# TTL_CAN.net
KiCad netlist of a schematic drawn in EasyEDA Pro
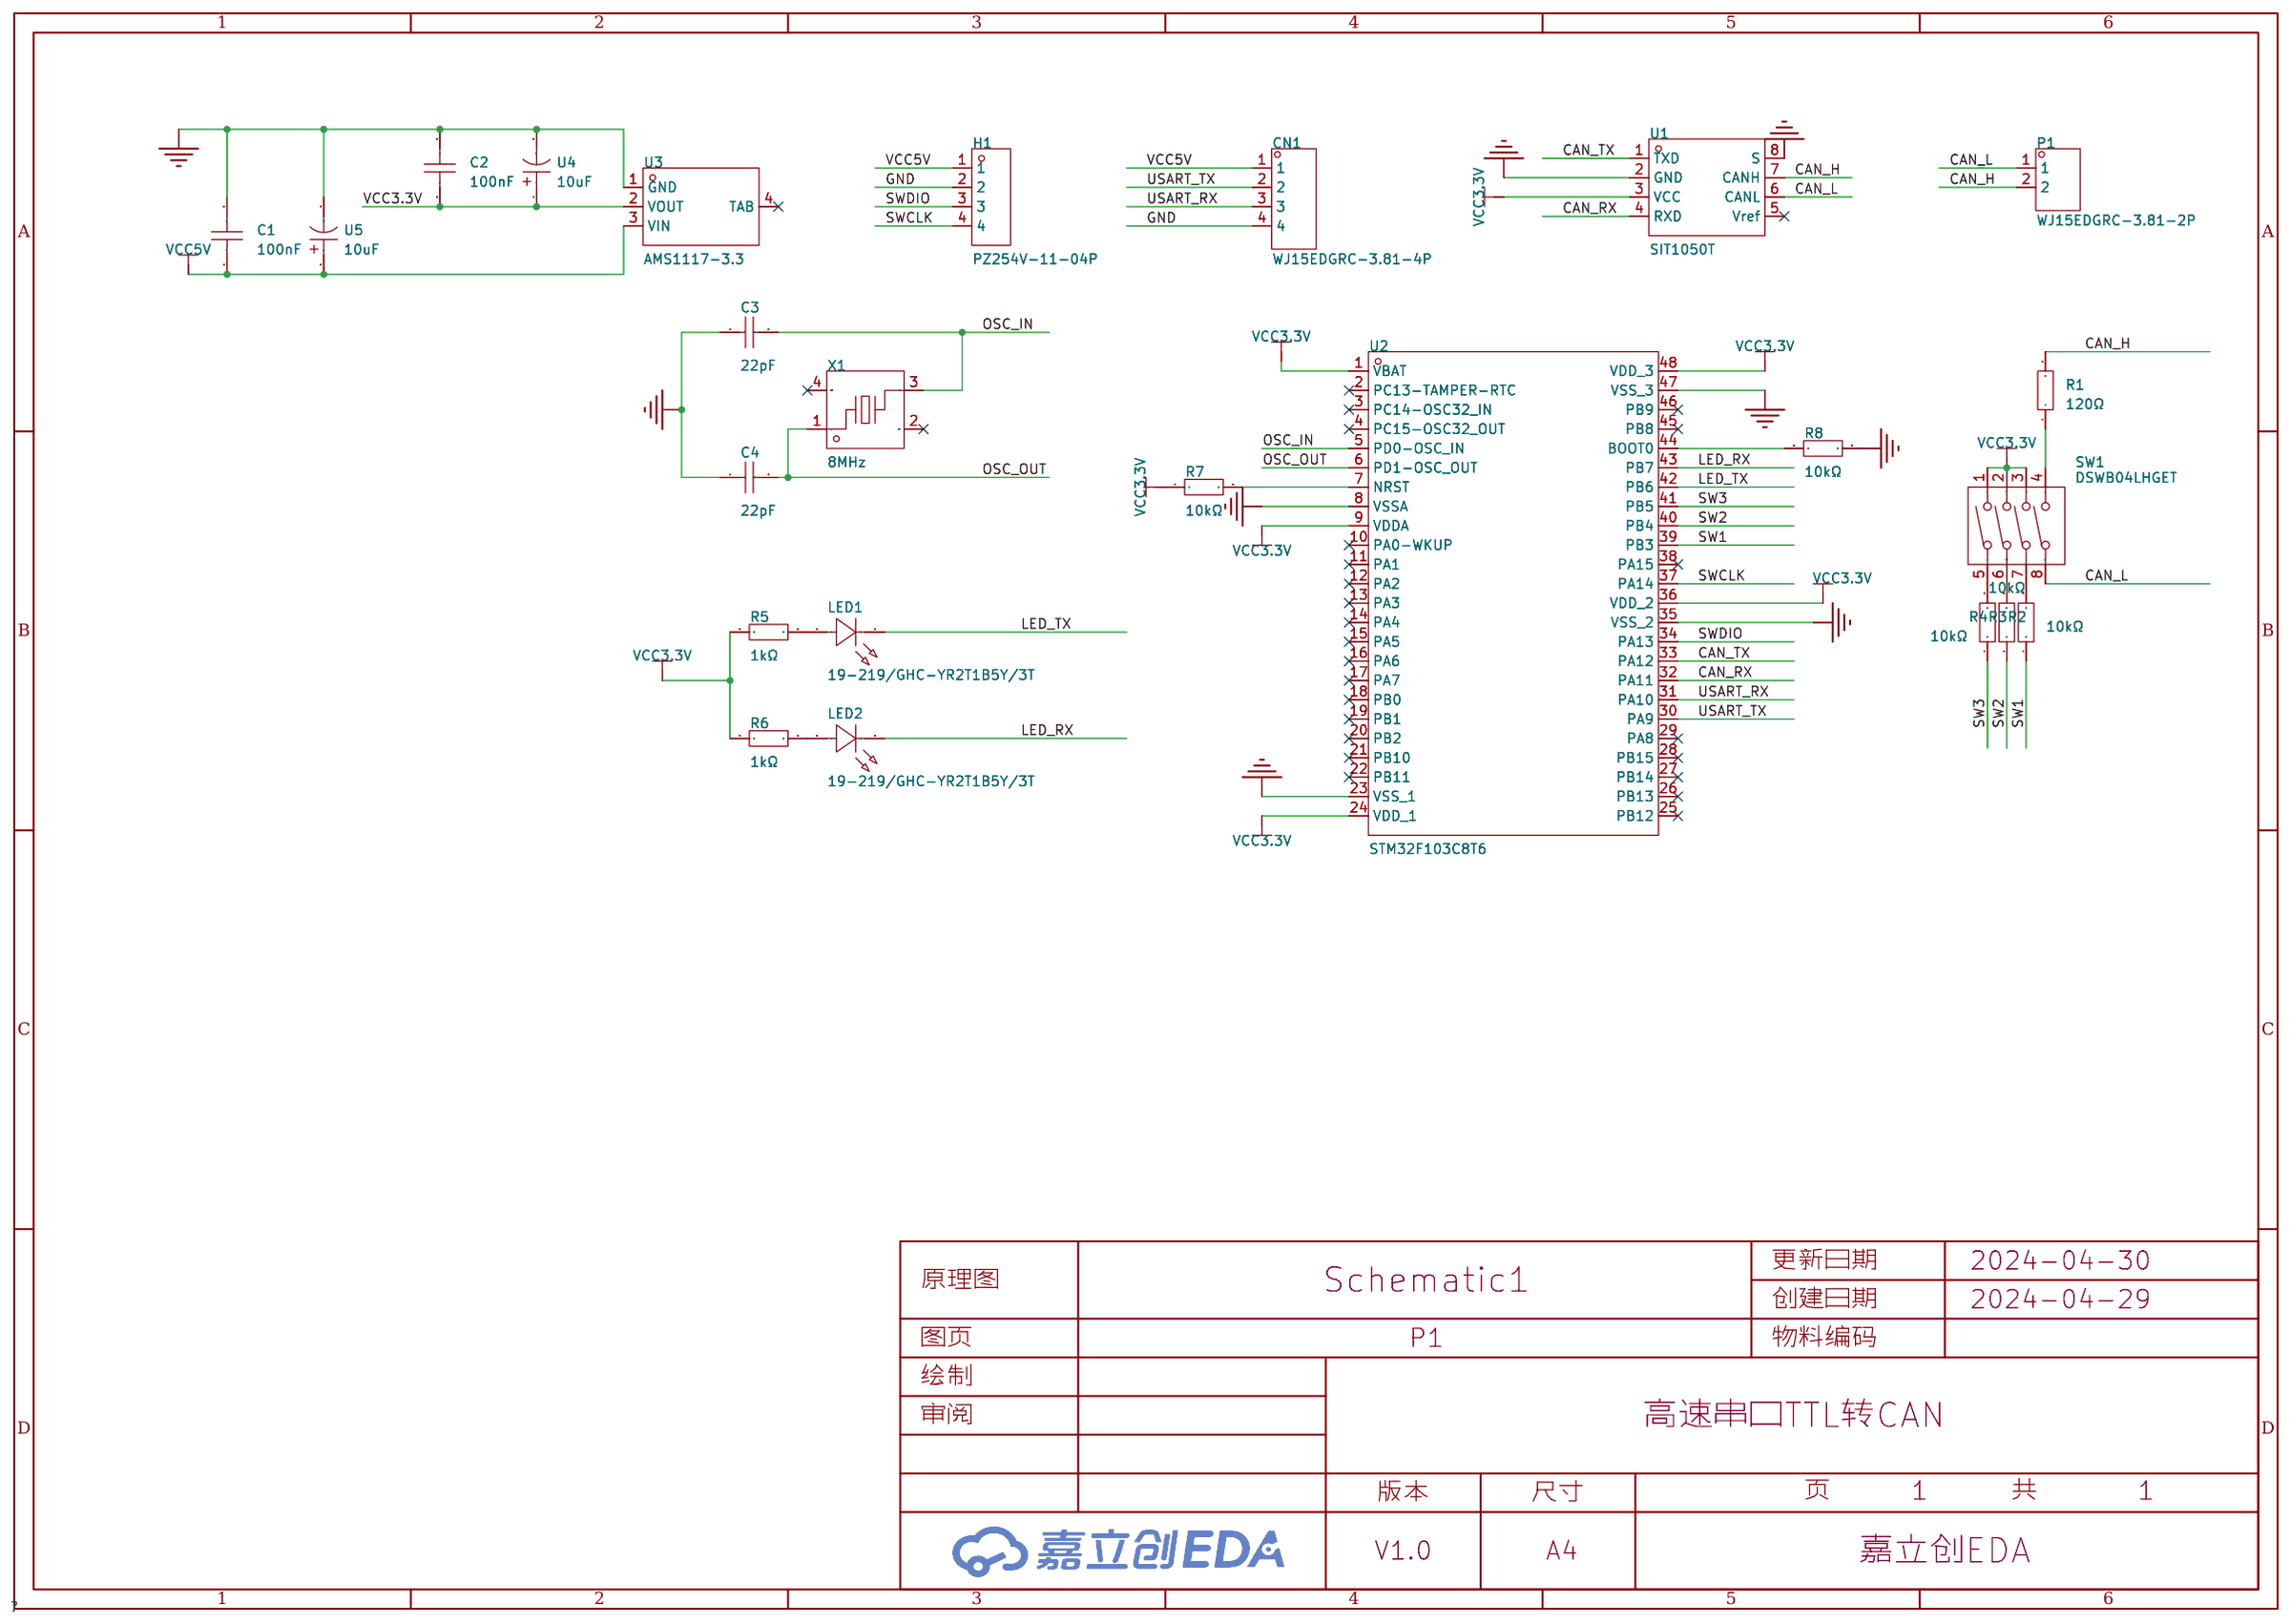
[diagram p0: schematic sheet]

(export (version "E")
  (design (tool "Eeschema 10.0.6"))
  (components
    (comp (ref "C1")
      (value "100nF")
      (footprint "easyedapro:C0603")
      (description "容值:100nF;精度:±10%;额定电压:50V;材质(温度系数):X7R;")
      (fields
        (field (name "Manufacturer Part") "CC0603KRX7R9BB104")
        (field (name "Manufacturer") "YAGEO(国巨)")
      )
      (libsource (lib "easyedapro") (part "CC0603KRX7R9BB104"))
    )
    (comp (ref "C2")
      (value "100nF")
      (footprint "easyedapro:C0603")
      (description "容值:100nF;精度:±10%;额定电压:50V;材质(温度系数):X7R;")
      (fields
        (field (name "Manufacturer Part") "CC0603KRX7R9BB104")
        (field (name "Manufacturer") "YAGEO(国巨)")
      )
      (libsource (lib "easyedapro") (part "CC0603KRX7R9BB104"))
    )
    (comp (ref "C3")
      (value "22pF")
      (footprint "easyedapro:C0603")
      (description "容值:22pF;精度:±5%;额定电压:50V;材质(温度系数):NP0;")
      (fields
        (field (name "Manufacturer Part") "CC0603JRNPO9BN220")
        (field (name "Manufacturer") "YAGEO(国巨)")
      )
      (libsource (lib "easyedapro") (part "CC0603JRNPO9BN220"))
    )
    (comp (ref "C4")
      (value "22pF")
      (footprint "easyedapro:C0603")
      (description "容值:22pF;精度:±5%;额定电压:50V;材质(温度系数):NP0;")
      (fields
        (field (name "Manufacturer Part") "CC0603JRNPO9BN220")
        (field (name "Manufacturer") "YAGEO(国巨)")
      )
      (libsource (lib "easyedapro") (part "CC0603JRNPO9BN220"))
    )
    (comp (ref "CN1")
      (value "WJ15EDGRC-3.81-4P")
      (footprint "easyedapro:CONN-TH_WJ15EDGRC-3.81-4P")
      (description "连接器类型:板端/插座-闭口;结构:1x4P;间距:3.81mm;颜色:绿色;安装方式:弯针;排数:1;每排PIN数:4;")
      (fields (field (name "Manufacturer") "KANGNEX(康奈克斯电气)"))
      (libsource (lib "easyedapro") (part "WJ15EDGRC-3.81-4P"))
    )
    (comp (ref "H1")
      (value "PZ254V-11-04P")
      (footprint "easyedapro:HDR-TH_4P-P2.54-V-M")
      (fields (field (name "Manufacturer") "XFCN(兴飞)"))
      (libsource (lib "easyedapro") (part "PZ254V-11-04P_C2691448"))
    )
    (comp (ref "LED1")
      (value "19-219/GHC-YR2T1B5Y/3T")
      (footprint "easyedapro:LED0603-RD_GREEN")
      (description "发光颜色:绿色;正向电流:20mA;主波长:518nm;透镜颜色:无色透明透镜;")
      (fields (field (name "Manufacturer") "EVERLIGHT(亿光)"))
      (libsource (lib "easyedapro") (part "19-219/GHC-YR2T1B5Y/3T"))
    )
    (comp (ref "LED2")
      (value "19-219/GHC-YR2T1B5Y/3T")
      (footprint "easyedapro:LED0603-RD_GREEN")
      (description "发光颜色:绿色;正向电流:20mA;主波长:518nm;透镜颜色:无色透明透镜;")
      (fields (field (name "Manufacturer") "EVERLIGHT(亿光)"))
      (libsource (lib "easyedapro") (part "19-219/GHC-YR2T1B5Y/3T"))
    )
    (comp (ref "P1")
      (value "WJ15EDGRC-3.81-2P")
      (footprint "easyedapro:CONN-TH_2P-P3.81_WJ15EDGRC-3.81-2P")
      (description "连接器类型:板端/插座-闭口;结构:1x2P;间距:3.81mm;颜色:绿色;安装方式:弯针;排数:1;每排PIN数:2;")
      (fields (field (name "Manufacturer") "KANGNEX(康奈克斯电气)"))
      (libsource (lib "easyedapro") (part "WJ15EDGRC-3.81-2P"))
    )
    (comp (ref "R1")
      (value "120Ω")
      (footprint "easyedapro:R0603")
      (description "电阻类型:厚膜电阻;阻值:120Ω;精度:±1%;功率:100mW;最大工作电压:75V;温度系数:±100ppm/°C;")
      (fields
        (field (name "Manufacturer Part") "0603WAF1200T5E")
        (field (name "Manufacturer") "UNI-ROYAL(厚声)")
      )
      (libsource (lib "easyedapro") (part "0603WAF1200T5E"))
    )
    (comp (ref "R2")
      (value "10kΩ")
      (footprint "easyedapro:R0603")
      (description "电阻类型:厚膜电阻;阻值:10kΩ;精度:±1%;功率:100mW;最大工作电压:75V;温度系数:±100ppm/°C;")
      (fields
        (field (name "Manufacturer Part") "0603WAF1002T5E")
        (field (name "Manufacturer") "UNI-ROYAL(厚声)")
      )
      (libsource (lib "easyedapro") (part "0603WAF1002T5E"))
    )
    (comp (ref "R3")
      (value "10kΩ")
      (footprint "easyedapro:R0603")
      (description "电阻类型:厚膜电阻;阻值:10kΩ;精度:±1%;功率:100mW;最大工作电压:75V;温度系数:±100ppm/°C;")
      (fields
        (field (name "Manufacturer Part") "0603WAF1002T5E")
        (field (name "Manufacturer") "UNI-ROYAL(厚声)")
      )
      (libsource (lib "easyedapro") (part "0603WAF1002T5E"))
    )
    (comp (ref "R4")
      (value "10kΩ")
      (footprint "easyedapro:R0603")
      (description "电阻类型:厚膜电阻;阻值:10kΩ;精度:±1%;功率:100mW;最大工作电压:75V;温度系数:±100ppm/°C;")
      (fields
        (field (name "Manufacturer Part") "0603WAF1002T5E")
        (field (name "Manufacturer") "UNI-ROYAL(厚声)")
      )
      (libsource (lib "easyedapro") (part "0603WAF1002T5E"))
    )
    (comp (ref "R5")
      (value "1kΩ")
      (footprint "easyedapro:R0603")
      (description "电阻类型:厚膜电阻;阻值:1kΩ;精度:±1%;功率:100mW;最大工作电压:75V;温度系数:±100ppm/°C;")
      (fields
        (field (name "Manufacturer Part") "0603WAF1001T5E")
        (field (name "Manufacturer") "UNI-ROYAL(厚声)")
      )
      (libsource (lib "easyedapro") (part "0603WAF1001T5E"))
    )
    (comp (ref "R6")
      (value "1kΩ")
      (footprint "easyedapro:R0603")
      (description "电阻类型:厚膜电阻;阻值:1kΩ;精度:±1%;功率:100mW;最大工作电压:75V;温度系数:±100ppm/°C;")
      (fields
        (field (name "Manufacturer Part") "0603WAF1001T5E")
        (field (name "Manufacturer") "UNI-ROYAL(厚声)")
      )
      (libsource (lib "easyedapro") (part "0603WAF1001T5E"))
    )
    (comp (ref "R7")
      (value "10kΩ")
      (footprint "easyedapro:R0603")
      (description "电阻类型:厚膜电阻;阻值:10kΩ;精度:±1%;功率:100mW;最大工作电压:75V;温度系数:±100ppm/°C;")
      (fields
        (field (name "Manufacturer Part") "0603WAF1002T5E")
        (field (name "Manufacturer") "UNI-ROYAL(厚声)")
      )
      (libsource (lib "easyedapro") (part "0603WAF1002T5E"))
    )
    (comp (ref "R8")
      (value "10kΩ")
      (footprint "easyedapro:R0603")
      (description "电阻类型:厚膜电阻;阻值:10kΩ;精度:±1%;功率:100mW;最大工作电压:75V;温度系数:±100ppm/°C;")
      (fields
        (field (name "Manufacturer Part") "0603WAF1002T5E")
        (field (name "Manufacturer") "UNI-ROYAL(厚声)")
      )
      (libsource (lib "easyedapro") (part "0603WAF1002T5E"))
    )
    (comp (ref "SW1")
      (value "DSWB04LHGET")
      (footprint "easyedapro:SW-TH_DSWB04LHGET")
      (description "类型:平拨,凸起式;电路结构:单刀单掷;开关位数:4位;使用寿命:-;颜色:红色;")
      (fields (field (name "Manufacturer") "YE"))
      (libsource (lib "easyedapro") (part "DSWB04LHGET"))
    )
    (comp (ref "U1")
      (value "SIT1050T")
      (footprint "easyedapro:SO-8_L4.9-W3.9-P1.27-LS5.9-BL")
      (description "类型:收发器;数据速率:1Mbps;")
      (fields (field (name "Manufacturer") "SIT(芯力特)"))
      (libsource (lib "easyedapro") (part "SIT1050T"))
    )
    (comp (ref "U2")
      (value "STM32F103C8T6")
      (footprint "easyedapro:LQFP-48_L7.0-W7.0-P0.50-LS9.0-BL")
      (description "CPU内核:CM3;程序存储容量:64KB;RAM总容量:20KB;GPIO端口数量:37;工作电压范围:2V~3.6V;CPU最大主频:72MHz;程序存储器类型:FLASH;")
      (fields (field (name "Manufacturer") "ST(意法半导体)"))
      (libsource (lib "easyedapro") (part "STM32F103C8T6"))
    )
    (comp (ref "U3")
      (value "AMS1117-3.3")
      (footprint "easyedapro:SOT-223-3_L6.5-W3.5-P3.05-LS7.0")
      (description "输出类型：固定 输出极性：正 最大输入电压：18V 输出电压：3.3V 输出电流：1A 电源纹波抑制比(PSRR)：60dB@(120Hz)。当前应用较多领域：三端稳压器，机顶盒")
      (fields (field (name "Manufacturer") "TWGMC(台湾迪嘉)"))
      (libsource (lib "easyedapro") (part "AMS1117-3.3_C5250992"))
    )
    (comp (ref "U4")
      (value "10uF")
      (footprint "easyedapro:CAP-SMD_L2.0-W1.3-FD")
      (description "容值:10uF;精度:±20%;额定电压:10V;等效串联电阻:6Ω@100kHz;")
      (fields (field (name "Manufacturer Part") "F921A106MPA") (field (name "Manufacturer") "Kyocera AVX"))
      (libsource (lib "easyedapro") (part "F921A106MPA"))
    )
    (comp (ref "U5")
      (value "10uF")
      (footprint "easyedapro:CAP-SMD_L2.0-W1.3-FD")
      (description "容值:10uF;精度:±20%;额定电压:10V;等效串联电阻:6Ω@100kHz;")
      (fields (field (name "Manufacturer Part") "F921A106MPA") (field (name "Manufacturer") "Kyocera AVX"))
      (libsource (lib "easyedapro") (part "F921A106MPA"))
    )
    (comp (ref "X1")
      (value "8MHz")
      (footprint "easyedapro:OSC-SMD_4P-L3.2-W2.5-BL")
      (description "晶振类型:贴片晶振;频率:8MHz;常温频差:±10ppm;外接负载电容:12pF;频率稳定度(全温):±20ppm;")
      (fields (field (name "Manufacturer Part") "X32258MOB4SI") (field (name "Manufacturer") "YXC(扬兴晶振)"))
      (libsource (lib "easyedapro") (part "X32258MOB4SI"))
    )
  )
  (nets
    (net (code "1") (name "/CAN_H") (class "Default")
      (node (ref "P1") (pin "2") (pinfunction "2_2") (pintype "input"))
      (node (ref "R1") (pin "2") (pinfunction "2_2") (pintype "input"))
      (node (ref "U1") (pin "7") (pinfunction "CANH_7") (pintype "input"))
    )
    (net (code "2") (name "/CAN_L") (class "Default")
      (node (ref "P1") (pin "1") (pinfunction "1_1") (pintype "input"))
      (node (ref "SW1") (pin "8") (pinfunction "8_8") (pintype "unspecified"))
      (node (ref "U1") (pin "6") (pinfunction "CANL_6") (pintype "input"))
    )
    (net (code "3") (name "/CAN_RX") (class "Default")
      (node (ref "U1") (pin "4") (pinfunction "RXD_4") (pintype "input"))
      (node (ref "U2") (pin "32") (pinfunction "PA11_32") (pintype "unspecified"))
    )
    (net (code "4") (name "/CAN_TX") (class "Default")
      (node (ref "U1") (pin "1") (pinfunction "TXD_1") (pintype "input"))
      (node (ref "U2") (pin "33") (pinfunction "PA12_33") (pintype "unspecified"))
    )
    (net (code "5") (name "/LED_RX") (class "Default")
      (node (ref "LED2") (pin "1") (pinfunction "K_1") (pintype "unspecified"))
      (node (ref "U2") (pin "43") (pinfunction "PB7_43") (pintype "unspecified"))
    )
    (net (code "6") (name "/LED_TX") (class "Default")
      (node (ref "LED1") (pin "1") (pinfunction "K_1") (pintype "unspecified"))
      (node (ref "U2") (pin "42") (pinfunction "PB6_42") (pintype "unspecified"))
    )
    (net (code "7") (name "/OSC_IN") (class "Default")
      (node (ref "C3") (pin "2") (pinfunction "2_2") (pintype "input"))
      (node (ref "U2") (pin "5") (pinfunction "PD0-OSC_IN_5") (pintype "unspecified"))
      (node (ref "X1") (pin "3") (pinfunction "3_3") (pintype "input"))
    )
    (net (code "8") (name "/OSC_OUT") (class "Default")
      (node (ref "C4") (pin "2") (pinfunction "2_2") (pintype "input"))
      (node (ref "U2") (pin "6") (pinfunction "PD1-OSC_OUT_6") (pintype "unspecified"))
      (node (ref "X1") (pin "1") (pinfunction "1_1") (pintype "input"))
    )
    (net (code "9") (name "/SW1") (class "Default")
      (node (ref "R2") (pin "1") (pinfunction "1_1") (pintype "input"))
      (node (ref "U2") (pin "39") (pinfunction "PB3_39") (pintype "unspecified"))
    )
    (net (code "10") (name "/SW2") (class "Default")
      (node (ref "R3") (pin "1") (pinfunction "1_1") (pintype "input"))
      (node (ref "U2") (pin "40") (pinfunction "PB4_40") (pintype "unspecified"))
    )
    (net (code "11") (name "/SW3") (class "Default")
      (node (ref "R4") (pin "1") (pinfunction "1_1") (pintype "input"))
      (node (ref "U2") (pin "41") (pinfunction "PB5_41") (pintype "unspecified"))
    )
    (net (code "12") (name "/SWCLK") (class "Default")
      (node (ref "H1") (pin "4") (pinfunction "4_4") (pintype "unspecified"))
      (node (ref "U2") (pin "37") (pinfunction "PA14_37") (pintype "unspecified"))
    )
    (net (code "13") (name "/SWDIO") (class "Default")
      (node (ref "H1") (pin "3") (pinfunction "3_3") (pintype "unspecified"))
      (node (ref "U2") (pin "34") (pinfunction "PA13_34") (pintype "unspecified"))
    )
    (net (code "14") (name "/USART_RX") (class "Default")
      (node (ref "CN1") (pin "3") (pinfunction "3_3") (pintype "unspecified"))
      (node (ref "U2") (pin "31") (pinfunction "PA10_31") (pintype "unspecified"))
    )
    (net (code "15") (name "/USART_TX") (class "Default")
      (node (ref "CN1") (pin "2") (pinfunction "2_2") (pintype "unspecified"))
      (node (ref "U2") (pin "30") (pinfunction "PA9_30") (pintype "unspecified"))
    )
    (net (code "16") (name "GND") (class "Default")
      (node (ref "C1") (pin "2") (pinfunction "2_2") (pintype "unspecified"))
      (node (ref "C2") (pin "2") (pinfunction "2_2") (pintype "unspecified"))
      (node (ref "C3") (pin "1") (pinfunction "1_1") (pintype "input"))
      (node (ref "C4") (pin "1") (pinfunction "1_1") (pintype "input"))
      (node (ref "CN1") (pin "4") (pinfunction "4_4") (pintype "unspecified"))
      (node (ref "H1") (pin "2") (pinfunction "2_2") (pintype "unspecified"))
      (node (ref "R8") (pin "2") (pinfunction "2_2") (pintype "input"))
      (node (ref "U1") (pin "2") (pinfunction "GND_2") (pintype "input"))
      (node (ref "U1") (pin "8") (pinfunction "S_8") (pintype "input"))
      (node (ref "U2") (pin "23") (pinfunction "VSS_1_23") (pintype "unspecified"))
      (node (ref "U2") (pin "35") (pinfunction "VSS_2_35") (pintype "unspecified"))
      (node (ref "U2") (pin "47") (pinfunction "VSS_3_47") (pintype "unspecified"))
      (node (ref "U2") (pin "8") (pinfunction "VSSA_8") (pintype "unspecified"))
      (node (ref "U3") (pin "1") (pinfunction "GND_1") (pintype "unspecified"))
      (node (ref "U4") (pin "2") (pinfunction "2_2") (pintype "input"))
      (node (ref "U5") (pin "2") (pinfunction "2_2") (pintype "input"))
    )
    (net (code "17") (name "Net-(LED1-A)") (class "Default")
      (node (ref "LED1") (pin "2") (pinfunction "A_2") (pintype "unspecified"))
      (node (ref "R5") (pin "2") (pinfunction "2_2") (pintype "input"))
    )
    (net (code "18") (name "Net-(LED2-A)") (class "Default")
      (node (ref "LED2") (pin "2") (pinfunction "A_2") (pintype "unspecified"))
      (node (ref "R6") (pin "2") (pinfunction "2_2") (pintype "input"))
    )
    (net (code "19") (name "Net-(R1-Pad1)") (class "Default")
      (node (ref "R1") (pin "1") (pinfunction "1_1") (pintype "input"))
      (node (ref "SW1") (pin "4") (pinfunction "4_4") (pintype "unspecified"))
    )
    (net (code "20") (name "Net-(R2-Pad2)") (class "Default")
      (node (ref "R2") (pin "2") (pinfunction "2_2") (pintype "input"))
      (node (ref "SW1") (pin "7") (pinfunction "7_7") (pintype "unspecified"))
    )
    (net (code "21") (name "Net-(R3-Pad2)") (class "Default")
      (node (ref "R3") (pin "2") (pinfunction "2_2") (pintype "input"))
      (node (ref "SW1") (pin "6") (pinfunction "6_6") (pintype "unspecified"))
    )
    (net (code "22") (name "Net-(R4-Pad2)") (class "Default")
      (node (ref "R4") (pin "2") (pinfunction "2_2") (pintype "input"))
      (node (ref "SW1") (pin "5") (pinfunction "5_5") (pintype "unspecified"))
    )
    (net (code "23") (name "Net-(U2-BOOT0)") (class "Default")
      (node (ref "R8") (pin "1") (pinfunction "1_1") (pintype "input"))
      (node (ref "U2") (pin "44") (pinfunction "BOOT0_44") (pintype "unspecified"))
    )
    (net (code "24") (name "Net-(U2-NRST)") (class "Default")
      (node (ref "R7") (pin "2") (pinfunction "2_2") (pintype "input"))
      (node (ref "U2") (pin "7") (pinfunction "NRST_7") (pintype "unspecified"))
    )
    (net (code "25") (name "VCC3.3V") (class "Default")
      (node (ref "C2") (pin "1") (pinfunction "1_1") (pintype "unspecified"))
      (node (ref "R5") (pin "1") (pinfunction "1_1") (pintype "input"))
      (node (ref "R6") (pin "1") (pinfunction "1_1") (pintype "input"))
      (node (ref "R7") (pin "1") (pinfunction "1_1") (pintype "input"))
      (node (ref "SW1") (pin "1") (pinfunction "1_1") (pintype "unspecified"))
      (node (ref "SW1") (pin "2") (pinfunction "2_2") (pintype "unspecified"))
      (node (ref "SW1") (pin "3") (pinfunction "3_3") (pintype "unspecified"))
      (node (ref "U1") (pin "3") (pinfunction "VCC_3") (pintype "input"))
      (node (ref "U2") (pin "1") (pinfunction "VBAT_1") (pintype "unspecified"))
      (node (ref "U2") (pin "24") (pinfunction "VDD_1_24") (pintype "unspecified"))
      (node (ref "U2") (pin "36") (pinfunction "VDD_2_36") (pintype "unspecified"))
      (node (ref "U2") (pin "48") (pinfunction "VDD_3_48") (pintype "unspecified"))
      (node (ref "U2") (pin "9") (pinfunction "VDDA_9") (pintype "unspecified"))
      (node (ref "U3") (pin "2") (pinfunction "VOUT_2") (pintype "unspecified"))
      (node (ref "U4") (pin "1") (pinfunction "1_1") (pintype "input"))
    )
    (net (code "26") (name "VCC5V") (class "Default")
      (node (ref "C1") (pin "1") (pinfunction "1_1") (pintype "unspecified"))
      (node (ref "CN1") (pin "1") (pinfunction "1_1") (pintype "unspecified"))
      (node (ref "H1") (pin "1") (pinfunction "1_1") (pintype "unspecified"))
      (node (ref "U3") (pin "3") (pinfunction "VIN_3") (pintype "unspecified"))
      (node (ref "U5") (pin "1") (pinfunction "1_1") (pintype "input"))
    )
    (net (code "27") (name "unconnected-(U1-Vref-Pad5)") (class "Default")
      (node (ref "U1") (pin "5") (pinfunction "Vref_5") (pintype "input+no_connect"))
    )
    (net (code "28") (name "unconnected-(U2-PA0-WKUP-Pad10)") (class "Default")
      (node (ref "U2") (pin "10") (pinfunction "PA0-WKUP_10") (pintype "unspecified+no_connect"))
    )
    (net (code "29") (name "unconnected-(U2-PA1-Pad11)") (class "Default")
      (node (ref "U2") (pin "11") (pinfunction "PA1_11") (pintype "unspecified+no_connect"))
    )
    (net (code "30") (name "unconnected-(U2-PA2-Pad12)") (class "Default")
      (node (ref "U2") (pin "12") (pinfunction "PA2_12") (pintype "unspecified+no_connect"))
    )
    (net (code "31") (name "unconnected-(U2-PA3-Pad13)") (class "Default")
      (node (ref "U2") (pin "13") (pinfunction "PA3_13") (pintype "unspecified+no_connect"))
    )
    (net (code "32") (name "unconnected-(U2-PA4-Pad14)") (class "Default")
      (node (ref "U2") (pin "14") (pinfunction "PA4_14") (pintype "unspecified+no_connect"))
    )
    (net (code "33") (name "unconnected-(U2-PA5-Pad15)") (class "Default")
      (node (ref "U2") (pin "15") (pinfunction "PA5_15") (pintype "unspecified+no_connect"))
    )
    (net (code "34") (name "unconnected-(U2-PA6-Pad16)") (class "Default")
      (node (ref "U2") (pin "16") (pinfunction "PA6_16") (pintype "unspecified+no_connect"))
    )
    (net (code "35") (name "unconnected-(U2-PA7-Pad17)") (class "Default")
      (node (ref "U2") (pin "17") (pinfunction "PA7_17") (pintype "unspecified+no_connect"))
    )
    (net (code "36") (name "unconnected-(U2-PA8-Pad29)") (class "Default")
      (node (ref "U2") (pin "29") (pinfunction "PA8_29") (pintype "unspecified+no_connect"))
    )
    (net (code "37") (name "unconnected-(U2-PA15-Pad38)") (class "Default")
      (node (ref "U2") (pin "38") (pinfunction "PA15_38") (pintype "unspecified+no_connect"))
    )
    (net (code "38") (name "unconnected-(U2-PB0-Pad18)") (class "Default")
      (node (ref "U2") (pin "18") (pinfunction "PB0_18") (pintype "unspecified+no_connect"))
    )
    (net (code "39") (name "unconnected-(U2-PB1-Pad19)") (class "Default")
      (node (ref "U2") (pin "19") (pinfunction "PB1_19") (pintype "unspecified+no_connect"))
    )
    (net (code "40") (name "unconnected-(U2-PB2-Pad20)") (class "Default")
      (node (ref "U2") (pin "20") (pinfunction "PB2_20") (pintype "unspecified+no_connect"))
    )
    (net (code "41") (name "unconnected-(U2-PB8-Pad45)") (class "Default")
      (node (ref "U2") (pin "45") (pinfunction "PB8_45") (pintype "unspecified+no_connect"))
    )
    (net (code "42") (name "unconnected-(U2-PB9-Pad46)") (class "Default")
      (node (ref "U2") (pin "46") (pinfunction "PB9_46") (pintype "unspecified+no_connect"))
    )
    (net (code "43") (name "unconnected-(U2-PB10-Pad21)") (class "Default")
      (node (ref "U2") (pin "21") (pinfunction "PB10_21") (pintype "unspecified+no_connect"))
    )
    (net (code "44") (name "unconnected-(U2-PB11-Pad22)") (class "Default")
      (node (ref "U2") (pin "22") (pinfunction "PB11_22") (pintype "unspecified+no_connect"))
    )
    (net (code "45") (name "unconnected-(U2-PB12-Pad25)") (class "Default")
      (node (ref "U2") (pin "25") (pinfunction "PB12_25") (pintype "unspecified+no_connect"))
    )
    (net (code "46") (name "unconnected-(U2-PB13-Pad26)") (class "Default")
      (node (ref "U2") (pin "26") (pinfunction "PB13_26") (pintype "unspecified+no_connect"))
    )
    (net (code "47") (name "unconnected-(U2-PB14-Pad27)") (class "Default")
      (node (ref "U2") (pin "27") (pinfunction "PB14_27") (pintype "unspecified+no_connect"))
    )
    (net (code "48") (name "unconnected-(U2-PB15-Pad28)") (class "Default")
      (node (ref "U2") (pin "28") (pinfunction "PB15_28") (pintype "unspecified+no_connect"))
    )
    (net (code "49") (name "unconnected-(U2-PC13-TAMPER-RTC-Pad2)") (class "Default")
      (node (ref "U2") (pin "2") (pinfunction "PC13-TAMPER-RTC_2") (pintype "unspecified+no_connect"))
    )
    (net (code "50") (name "unconnected-(U2-PC14-OSC32_IN-Pad3)") (class "Default")
      (node (ref "U2") (pin "3") (pinfunction "PC14-OSC32_IN_3") (pintype "unspecified+no_connect"))
    )
    (net (code "51") (name "unconnected-(U2-PC15-OSC32_OUT-Pad4)") (class "Default")
      (node (ref "U2") (pin "4") (pinfunction "PC15-OSC32_OUT_4") (pintype "unspecified+no_connect"))
    )
    (net (code "52") (name "unconnected-(U3-TAB-Pad4)") (class "Default")
      (node (ref "U3") (pin "4") (pinfunction "TAB_4") (pintype "unspecified+no_connect"))
    )
    (net (code "53") (name "unconnected-(X1-GND-Pad2)") (class "Default")
      (node (ref "X1") (pin "2") (pinfunction "GND_2") (pintype "input+no_connect"))
    )
    (net (code "54") (name "unconnected-(X1-GND-Pad4)") (class "Default")
      (node (ref "X1") (pin "4") (pinfunction "GND_4") (pintype "input+no_connect"))
    )
  )
)
